# TSOP-II-44.net
KiCad netlist of a schematic drawn in EAGLE
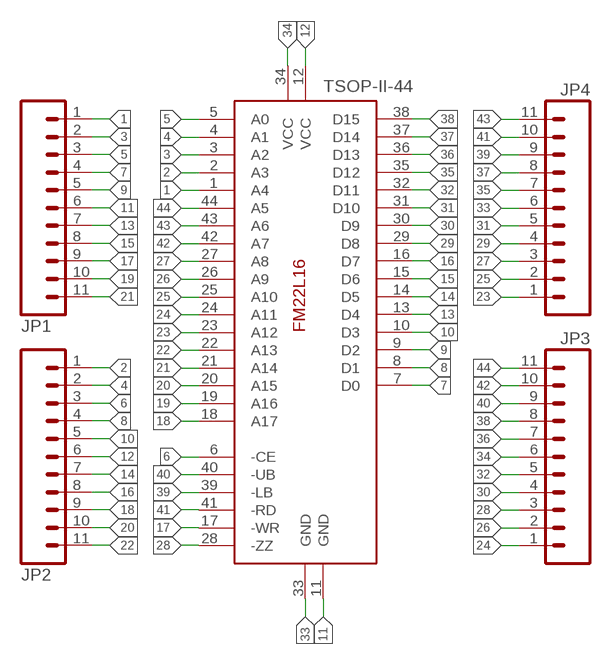
[diagram p0: schematic, sheet 1]

(export (version "E")
  (design (tool "Eeschema 10.0.6"))
  (components
    (comp (ref "JP1")
      (value "M11PTH")
      (footprint "eagle-import:1X11")
      (libsource (lib "eagle-import") (part "M11PTH"))
    )
    (comp (ref "JP2")
      (value "M11PTH")
      (footprint "eagle-import:1X11")
      (libsource (lib "eagle-import") (part "M11PTH"))
    )
    (comp (ref "JP3")
      (value "M11PTH")
      (footprint "eagle-import:1X11")
      (libsource (lib "eagle-import") (part "M11PTH"))
    )
    (comp (ref "JP4")
      (value "M11PTH")
      (footprint "eagle-import:1X11")
      (libsource (lib "eagle-import") (part "M11PTH"))
    )
    (comp (ref "TSOP-II-44")
      (value "FM22L16-TG")
      (footprint "eagle-import:TSOPII-44")
      (libsource (lib "eagle-import") (part "FM22L16-TG"))
    )
  )
  (nets
    (net (code "1") (name "1") (class "Default")
      (node (ref "JP1") (pin "1") (pinfunction "1_1") (pintype "passive"))
      (node (ref "TSOP-II-44") (pin "1") (pinfunction "A4_1") (pintype "input"))
    )
    (net (code "2") (name "2") (class "Default")
      (node (ref "JP2") (pin "1") (pinfunction "1_1") (pintype "passive"))
      (node (ref "TSOP-II-44") (pin "2") (pinfunction "A3_2") (pintype "input"))
    )
    (net (code "3") (name "3") (class "Default")
      (node (ref "JP1") (pin "2") (pinfunction "2_2") (pintype "passive"))
      (node (ref "TSOP-II-44") (pin "3") (pinfunction "A2_3") (pintype "input"))
    )
    (net (code "4") (name "4") (class "Default")
      (node (ref "JP2") (pin "2") (pinfunction "2_2") (pintype "passive"))
      (node (ref "TSOP-II-44") (pin "4") (pinfunction "A1_4") (pintype "input"))
    )
    (net (code "5") (name "5") (class "Default")
      (node (ref "JP1") (pin "3") (pinfunction "3_3") (pintype "passive"))
      (node (ref "TSOP-II-44") (pin "5") (pinfunction "A0_5") (pintype "input"))
    )
    (net (code "6") (name "6") (class "Default")
      (node (ref "JP2") (pin "3") (pinfunction "3_3") (pintype "passive"))
      (node (ref "TSOP-II-44") (pin "6") (pinfunction "-CE_6") (pintype "input"))
    )
    (net (code "7") (name "7") (class "Default")
      (node (ref "JP1") (pin "4") (pinfunction "4_4") (pintype "passive"))
      (node (ref "TSOP-II-44") (pin "7") (pinfunction "D0_7") (pintype "bidirectional"))
    )
    (net (code "8") (name "8") (class "Default")
      (node (ref "JP2") (pin "4") (pinfunction "4_4") (pintype "passive"))
      (node (ref "TSOP-II-44") (pin "8") (pinfunction "D1_8") (pintype "bidirectional"))
    )
    (net (code "9") (name "9") (class "Default")
      (node (ref "JP1") (pin "5") (pinfunction "5_5") (pintype "passive"))
      (node (ref "TSOP-II-44") (pin "9") (pinfunction "D2_9") (pintype "bidirectional"))
    )
    (net (code "10") (name "10") (class "Default")
      (node (ref "JP2") (pin "5") (pinfunction "5_5") (pintype "passive"))
      (node (ref "TSOP-II-44") (pin "10") (pinfunction "D3_10") (pintype "bidirectional"))
    )
    (net (code "11") (name "11") (class "Default")
      (node (ref "JP1") (pin "6") (pinfunction "6_6") (pintype "passive"))
      (node (ref "TSOP-II-44") (pin "11") (pinfunction "GND_11") (pintype "power_in"))
    )
    (net (code "12") (name "12") (class "Default")
      (node (ref "JP2") (pin "6") (pinfunction "6_6") (pintype "passive"))
      (node (ref "TSOP-II-44") (pin "12") (pinfunction "VCC_12") (pintype "power_in"))
    )
    (net (code "13") (name "13") (class "Default")
      (node (ref "JP1") (pin "7") (pinfunction "7_7") (pintype "passive"))
      (node (ref "TSOP-II-44") (pin "13") (pinfunction "D4_13") (pintype "bidirectional"))
    )
    (net (code "14") (name "14") (class "Default")
      (node (ref "JP2") (pin "7") (pinfunction "7_7") (pintype "passive"))
      (node (ref "TSOP-II-44") (pin "14") (pinfunction "D5_14") (pintype "bidirectional"))
    )
    (net (code "15") (name "15") (class "Default")
      (node (ref "JP1") (pin "8") (pinfunction "8_8") (pintype "passive"))
      (node (ref "TSOP-II-44") (pin "15") (pinfunction "D6_15") (pintype "bidirectional"))
    )
    (net (code "16") (name "16") (class "Default")
      (node (ref "JP2") (pin "8") (pinfunction "8_8") (pintype "passive"))
      (node (ref "TSOP-II-44") (pin "16") (pinfunction "D7_16") (pintype "bidirectional"))
    )
    (net (code "17") (name "17") (class "Default")
      (node (ref "JP1") (pin "9") (pinfunction "9_9") (pintype "passive"))
      (node (ref "TSOP-II-44") (pin "17") (pinfunction "-WR_17") (pintype "input"))
    )
    (net (code "18") (name "18") (class "Default")
      (node (ref "JP2") (pin "9") (pinfunction "9_9") (pintype "passive"))
      (node (ref "TSOP-II-44") (pin "18") (pinfunction "A17_18") (pintype "input"))
    )
    (net (code "19") (name "19") (class "Default")
      (node (ref "JP1") (pin "10") (pinfunction "10_10") (pintype "passive"))
      (node (ref "TSOP-II-44") (pin "19") (pinfunction "A16_19") (pintype "input"))
    )
    (net (code "20") (name "20") (class "Default")
      (node (ref "JP2") (pin "10") (pinfunction "10_10") (pintype "passive"))
      (node (ref "TSOP-II-44") (pin "20") (pinfunction "A15_20") (pintype "input"))
    )
    (net (code "21") (name "21") (class "Default")
      (node (ref "JP1") (pin "11") (pinfunction "11_11") (pintype "passive"))
      (node (ref "TSOP-II-44") (pin "21") (pinfunction "A14_21") (pintype "input"))
    )
    (net (code "22") (name "22") (class "Default")
      (node (ref "JP2") (pin "11") (pinfunction "11_11") (pintype "passive"))
      (node (ref "TSOP-II-44") (pin "22") (pinfunction "A13_22") (pintype "input"))
    )
    (net (code "23") (name "23") (class "Default")
      (node (ref "JP4") (pin "1") (pinfunction "1_1") (pintype "passive"))
      (node (ref "TSOP-II-44") (pin "23") (pinfunction "A12_23") (pintype "input"))
    )
    (net (code "24") (name "24") (class "Default")
      (node (ref "JP3") (pin "1") (pinfunction "1_1") (pintype "passive"))
      (node (ref "TSOP-II-44") (pin "24") (pinfunction "A11_24") (pintype "input"))
    )
    (net (code "25") (name "25") (class "Default")
      (node (ref "JP4") (pin "2") (pinfunction "2_2") (pintype "passive"))
      (node (ref "TSOP-II-44") (pin "25") (pinfunction "A10_25") (pintype "input"))
    )
    (net (code "26") (name "26") (class "Default")
      (node (ref "JP3") (pin "2") (pinfunction "2_2") (pintype "passive"))
      (node (ref "TSOP-II-44") (pin "26") (pinfunction "A9_26") (pintype "input"))
    )
    (net (code "27") (name "27") (class "Default")
      (node (ref "JP4") (pin "3") (pinfunction "3_3") (pintype "passive"))
      (node (ref "TSOP-II-44") (pin "27") (pinfunction "A8_27") (pintype "input"))
    )
    (net (code "28") (name "28") (class "Default")
      (node (ref "JP3") (pin "3") (pinfunction "3_3") (pintype "passive"))
      (node (ref "TSOP-II-44") (pin "28") (pinfunction "-ZZ_28") (pintype "input"))
    )
    (net (code "29") (name "29") (class "Default")
      (node (ref "JP4") (pin "4") (pinfunction "4_4") (pintype "passive"))
      (node (ref "TSOP-II-44") (pin "29") (pinfunction "D8_29") (pintype "bidirectional"))
    )
    (net (code "30") (name "30") (class "Default")
      (node (ref "JP3") (pin "4") (pinfunction "4_4") (pintype "passive"))
      (node (ref "TSOP-II-44") (pin "30") (pinfunction "D9_30") (pintype "bidirectional"))
    )
    (net (code "31") (name "31") (class "Default")
      (node (ref "JP4") (pin "5") (pinfunction "5_5") (pintype "passive"))
      (node (ref "TSOP-II-44") (pin "31") (pinfunction "D10_31") (pintype "bidirectional"))
    )
    (net (code "32") (name "32") (class "Default")
      (node (ref "JP3") (pin "5") (pinfunction "5_5") (pintype "passive"))
      (node (ref "TSOP-II-44") (pin "32") (pinfunction "D11_32") (pintype "bidirectional"))
    )
    (net (code "33") (name "33") (class "Default")
      (node (ref "JP4") (pin "6") (pinfunction "6_6") (pintype "passive"))
      (node (ref "TSOP-II-44") (pin "33") (pinfunction "GND_33") (pintype "power_in"))
    )
    (net (code "34") (name "34") (class "Default")
      (node (ref "JP3") (pin "6") (pinfunction "6_6") (pintype "passive"))
      (node (ref "TSOP-II-44") (pin "34") (pinfunction "VCC_34") (pintype "power_in"))
    )
    (net (code "35") (name "35") (class "Default")
      (node (ref "JP4") (pin "7") (pinfunction "7_7") (pintype "passive"))
      (node (ref "TSOP-II-44") (pin "35") (pinfunction "D12_35") (pintype "bidirectional"))
    )
    (net (code "36") (name "36") (class "Default")
      (node (ref "JP3") (pin "7") (pinfunction "7_7") (pintype "passive"))
      (node (ref "TSOP-II-44") (pin "36") (pinfunction "D13_36") (pintype "bidirectional"))
    )
    (net (code "37") (name "37") (class "Default")
      (node (ref "JP4") (pin "8") (pinfunction "8_8") (pintype "passive"))
      (node (ref "TSOP-II-44") (pin "37") (pinfunction "D14_37") (pintype "bidirectional"))
    )
    (net (code "38") (name "38") (class "Default")
      (node (ref "JP3") (pin "8") (pinfunction "8_8") (pintype "passive"))
      (node (ref "TSOP-II-44") (pin "38") (pinfunction "D15_38") (pintype "bidirectional"))
    )
    (net (code "39") (name "39") (class "Default")
      (node (ref "JP4") (pin "9") (pinfunction "9_9") (pintype "passive"))
      (node (ref "TSOP-II-44") (pin "39") (pinfunction "-LB_39") (pintype "input"))
    )
    (net (code "40") (name "40") (class "Default")
      (node (ref "JP3") (pin "9") (pinfunction "9_9") (pintype "passive"))
      (node (ref "TSOP-II-44") (pin "40") (pinfunction "-UB_40") (pintype "input"))
    )
    (net (code "41") (name "41") (class "Default")
      (node (ref "JP4") (pin "10") (pinfunction "10_10") (pintype "passive"))
      (node (ref "TSOP-II-44") (pin "41") (pinfunction "-RD_41") (pintype "input"))
    )
    (net (code "42") (name "42") (class "Default")
      (node (ref "JP3") (pin "10") (pinfunction "10_10") (pintype "passive"))
      (node (ref "TSOP-II-44") (pin "42") (pinfunction "A7_42") (pintype "input"))
    )
    (net (code "43") (name "43") (class "Default")
      (node (ref "JP4") (pin "11") (pinfunction "11_11") (pintype "passive"))
      (node (ref "TSOP-II-44") (pin "43") (pinfunction "A6_43") (pintype "input"))
    )
    (net (code "44") (name "44") (class "Default")
      (node (ref "JP3") (pin "11") (pinfunction "11_11") (pintype "passive"))
      (node (ref "TSOP-II-44") (pin "44") (pinfunction "A5_44") (pintype "input"))
    )
  )
)
